# ONTVANGER.net
KiCad netlist of a schematic drawn in Altium Designer
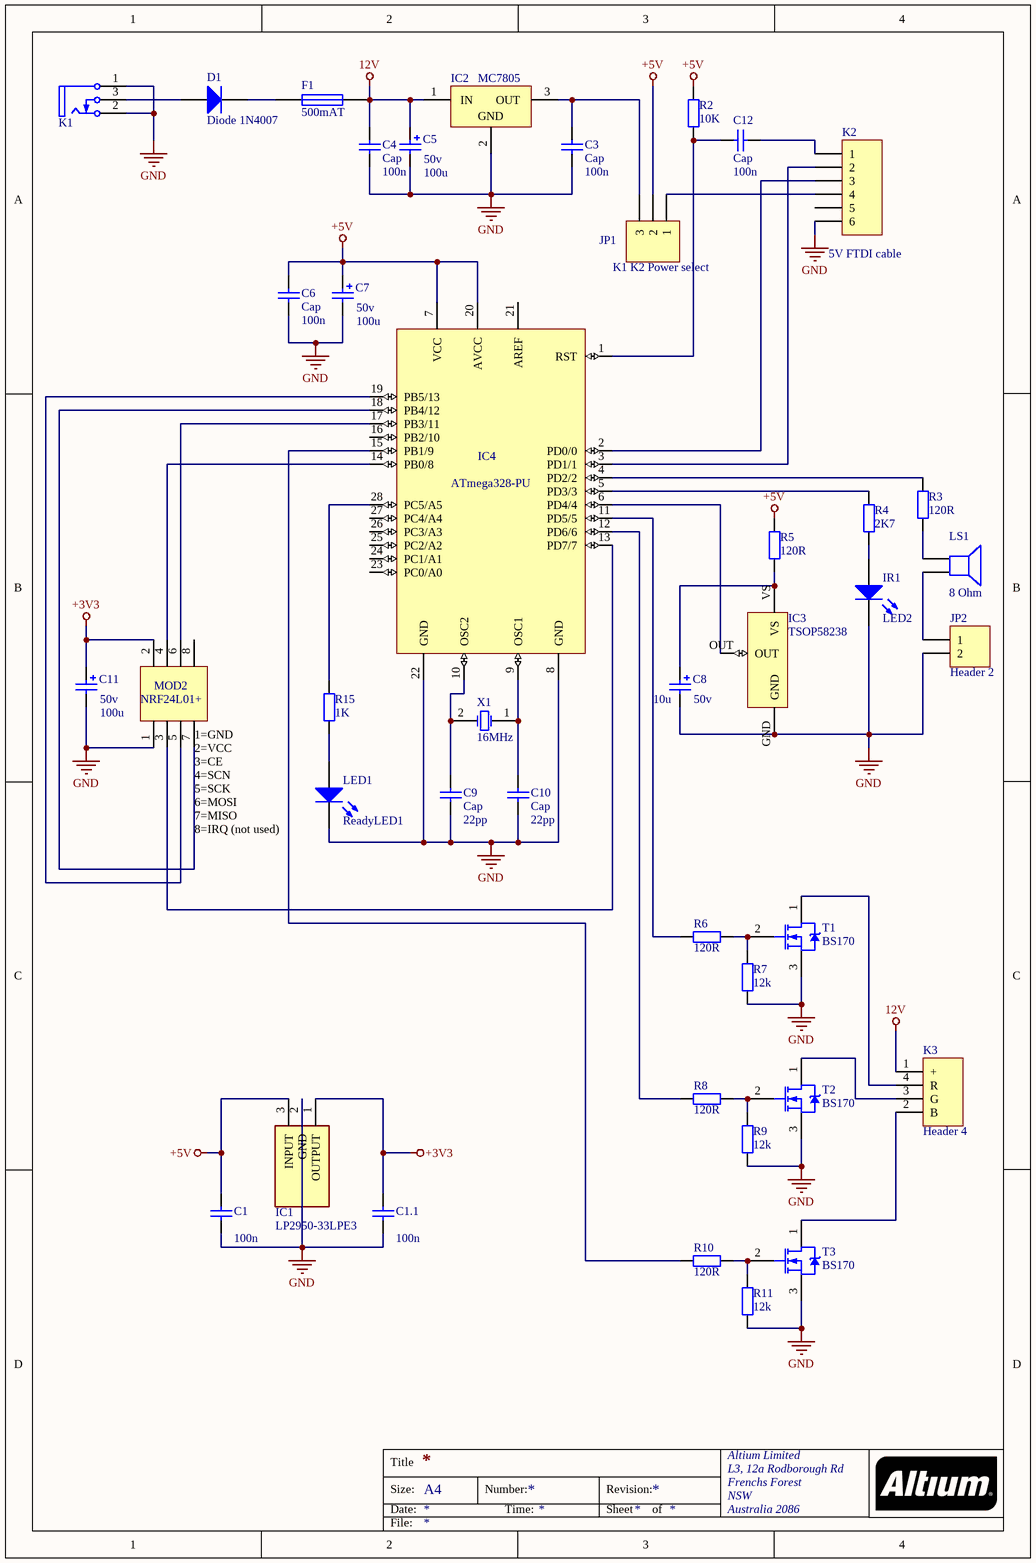
[diagram p0: ONTVANGER.SchDoc]

(export (version "E")
  (design (tool "Eeschema 10.0.6"))
  (components
    (comp (ref "C1")
      (value "100n")
      (footprint "RAD-0.3")
      (description "Capacitor")
      (fields (field (name "Comment") "Cap") (field (name "PUBLISHER") "Altium Limited"))
      (libsource (lib "Miscellaneous Devices") (part "Cap"))
    )
    (comp (ref "C1.1")
      (value "100n")
      (footprint "RAD-0.3")
      (description "Capacitor")
      (fields (field (name "Comment") "Cap") (field (name "PUBLISHER") "Altium Limited"))
      (libsource (lib "Miscellaneous Devices") (part "Cap"))
    )
    (comp (ref "C3")
      (value "Cap")
      (footprint "RAD-0.3")
      (description "Capacitor")
      (fields (field (name "ALTIUM_VALUE") "100n") (field (name "PUBLISHER") "Altium Limited"))
      (libsource (lib "Miscellaneous Devices") (part "Cap"))
    )
    (comp (ref "C4")
      (value "Cap")
      (footprint "RAD-0.3")
      (description "Capacitor")
      (fields (field (name "ALTIUM_VALUE") "100n") (field (name "PUBLISHER") "Altium Limited"))
      (libsource (lib "Miscellaneous Devices") (part "Cap"))
    )
    (comp (ref "C5")
      (value "50v")
      (footprint "POLAR0.8")
      (description "Polarized Capacitor (Axial)")
      (fields (field (name "ALTIUM_VALUE") "100u") (field (name "PUBLISHER") "Altium Limited"))
      (libsource (lib "Miscellaneous Devices") (part "Cap Pol2"))
    )
    (comp (ref "C6")
      (value "Cap")
      (footprint "RAD-0.3")
      (description "Capacitor")
      (fields (field (name "ALTIUM_VALUE") "100n") (field (name "PUBLISHER") "Altium Limited"))
      (libsource (lib "Miscellaneous Devices") (part "Cap"))
    )
    (comp (ref "C7")
      (value "50v")
      (footprint "POLAR0.8")
      (description "Polarized Capacitor (Axial)")
      (fields (field (name "ALTIUM_VALUE") "100u") (field (name "PUBLISHER") "Altium Limited"))
      (libsource (lib "Miscellaneous Devices") (part "Cap Pol2"))
    )
    (comp (ref "C8")
      (value "50v")
      (footprint "POLAR0.8")
      (description "Polarized Capacitor (Axial)")
      (fields (field (name "ALTIUM_VALUE") "10u") (field (name "PUBLISHER") "Altium Limited"))
      (libsource (lib "Miscellaneous Devices") (part "Cap Pol2"))
    )
    (comp (ref "C9")
      (value "Cap")
      (footprint "RAD-0.3")
      (description "Capacitor")
      (fields (field (name "ALTIUM_VALUE") "22pp") (field (name "PUBLISHER") "Altium Limited"))
      (libsource (lib "Miscellaneous Devices") (part "Cap"))
    )
    (comp (ref "C10")
      (value "Cap")
      (footprint "RAD-0.3")
      (description "Capacitor")
      (fields (field (name "ALTIUM_VALUE") "22pp") (field (name "PUBLISHER") "Altium Limited"))
      (libsource (lib "Miscellaneous Devices") (part "Cap"))
    )
    (comp (ref "C11")
      (value "50v")
      (footprint "POLAR0.8")
      (description "Polarized Capacitor (Axial)")
      (fields (field (name "ALTIUM_VALUE") "100u") (field (name "PUBLISHER") "Altium Limited"))
      (libsource (lib "Miscellaneous Devices") (part "Cap Pol2"))
    )
    (comp (ref "C12")
      (value "Cap")
      (footprint "RAD-0.3")
      (description "Capacitor")
      (fields (field (name "ALTIUM_VALUE") "100n") (field (name "PUBLISHER") "Altium Limited"))
      (libsource (lib "Miscellaneous Devices") (part "Cap"))
    )
    (comp (ref "D1")
      (value "Diode 1N4007")
      (footprint "DO-41")
      (description "1 Amp General Purpose Rectifier")
      (fields (field (name "PUBLISHER") "Altium Limited"))
      (libsource (lib "Miscellaneous Devices") (part "Diode 1N4007"))
    )
    (comp (ref "F1")
      (value "500mAT")
      (footprint "PIN-W2/E2.8")
      (description "Fuse")
      (fields (field (name "PUBLISHER") "Altium Limited"))
      (libsource (lib "Miscellaneous Devices") (part "Fuse 1"))
    )
    (comp (ref "IC1")
      (value "LP2950-33LPE3")
      (footprint "SamacSys:TO127P419X482X788-3P")
      (description "Integrated Circuit")
      (fields
        (field (name "MOUSER PART NUMBER") "595-LP2950-33LPE3")
        (field (name "RS PART NUMBER") "7620430P")
      )
      (libsource (lib "*") (part "LP2950-33LPE3"))
    )
    (comp (ref "IC2")
      (value "MC7805")
      (footprint "ONSC-TO-220-3-221AB-01")
      (description "Positive Voltage Regulator, 1 A, 5 V, 0 to 125 degC, 3-Pin TO-220, RoHS, Tube")
      (fields (field (name "MANUFACTURER") "ON Semiconductor"))
      (libsource (lib "Altium Content Vault") (part "ONSC-MC7805CTG-TO-220-3"))
    )
    (comp (ref "IC3")
      (value "TSOP58238")
      (footprint "*TSOP-382_TSOP38238(Primary)")
      (description "IR Receiver Modules for Remote Control System, 2.5 to 5.5 V, -25 to 85 degC, 3-Pin THD, RoHS, Bulk")
      (fields (field (name "TOLERANCE") "30ppm") (field (name "MANUFACTURER") "Vishay"))
      (libsource (lib "PCB_Project_1") (part "CMP-1666-00022-1"))
    )
    (comp (ref "IC4")
      (value "ATmega328-PU")
      (footprint "*DIL28")
      (fields
        (field (name "MANUFACTURER") "Microchip / Atmel")
        (field (name "MANUFACTURER PART NUMBER") "ATMEGA328-PU")
      )
      (libsource (lib "PCB_Project") (part "CMP-0095-00015-2"))
    )
    (comp (ref "IR1")
      (value "LED2")
      (footprint "LED-0")
      (description "Typical INFRARED GaAs LED")
      (fields (field (name "PUBLISHER") "Altium Limited"))
      (libsource (lib "Miscellaneous Devices") (part "LED0"))
    )
    (comp (ref "JP1")
      (value "K1 K2 Power select")
      (footprint "HDR1X3")
      (description "Header, 3-Pin")
      (fields (field (name "PUBLISHER") "Altium Limited"))
      (libsource (lib "Miscellaneous Connectors") (part "Header 3"))
    )
    (comp (ref "JP2")
      (value "Header 2")
      (footprint "HDR1X2")
      (description "Header, 2-Pin")
      (fields (field (name "PUBLISHER") "Altium Limited"))
      (libsource (lib "Miscellaneous Connectors") (part "Header 2"))
    )
    (comp (ref "K1")
      (value "PJRAN1X1U01X")
      (footprint "SWIT-PJRAN1X1U01X_V")
      (description "Female Phono Jack, 3 Position, Height 13 mm, Tail Length 4 mm, RoHS, Bulk")
      (fields (field (name "TOLERANCE") "10%"))
      (libsource (lib "Altium Content Vault") (part "JACK-2CD3-TN"))
    )
    (comp (ref "K2")
      (value "5V FTDI cable")
      (footprint "HDR1X6")
      (description "Header, 6-Pin")
      (fields (field (name "PUBLISHER") "Altium Limited"))
      (libsource (lib "Miscellaneous Connectors") (part "Header 6"))
    )
    (comp (ref "K3")
      (value "Header 4")
      (footprint "HDR1X4")
      (description "Header, 4-Pin")
      (fields (field (name "PUBLISHER") "Altium Limited"))
      (libsource (lib "Miscellaneous Connectors") (part "Header 4"))
    )
    (comp (ref "LS1")
      (value "8 Ohm")
      (footprint "PIN2")
      (description "Loudspeaker")
      (fields (field (name "PUBLISHER") "Altium Limited"))
      (libsource (lib "Miscellaneous Devices") (part "Speaker"))
    )
    (comp (ref "MOD2")
      (value "NRF24L01+")
      (footprint "HDR2X4")
      (description "Header, 4-Pin, Dual row")
      (fields (field (name "PUBLISHER") "Altium Limited"))
      (libsource (lib "Miscellaneous Connectors") (part "Header 4X2"))
    )
    (comp (ref "R2")
      (value "10K")
      (footprint "*RESC3115X70N")
      (description "Resistor")
      (fields (field (name "Comment") "Res2") (field (name "PUBLISHER") "Altium Limited"))
      (libsource (lib "PCB_Project") (part "Res2"))
    )
    (comp (ref "R3")
      (value "120R")
      (footprint "*RESC3146X60N")
      (description "Resistor")
      (fields (field (name "Comment") "Res2") (field (name "PUBLISHER") "Altium Limited"))
      (libsource (lib "PCB_Project") (part "Res2"))
    )
    (comp (ref "R4")
      (value "2K7")
      (footprint "*RESC3215X64N")
      (description "Resistor")
      (fields (field (name "Comment") "Res2") (field (name "PUBLISHER") "Altium Limited"))
      (libsource (lib "PCB_Project") (part "Res2"))
    )
    (comp (ref "R5")
      (value "120R")
      (footprint "*RESC3146X60N")
      (description "Resistor")
      (fields (field (name "Comment") "Res2") (field (name "PUBLISHER") "Altium Limited"))
      (libsource (lib "PCB_Project") (part "Res2"))
    )
    (comp (ref "R6")
      (value "120R")
      (footprint "*RESC3146X60N")
      (description "Resistor")
      (fields (field (name "Comment") "Res2") (field (name "PUBLISHER") "Altium Limited"))
      (libsource (lib "") (part "Res2_1"))
    )
    (comp (ref "R7")
      (value "12k")
      (footprint "*RESC3215X64N")
      (description "Resistor")
      (fields (field (name "Comment") "Res2") (field (name "PUBLISHER") "Altium Limited"))
      (libsource (lib "PCB_Project") (part "Res2"))
    )
    (comp (ref "R8")
      (value "120R")
      (footprint "*RESC3146X60N")
      (description "Resistor")
      (fields (field (name "Comment") "Res2") (field (name "PUBLISHER") "Altium Limited"))
      (libsource (lib "") (part "Res2_1"))
    )
    (comp (ref "R9")
      (value "12k")
      (footprint "*RESC3215X64N")
      (description "Resistor")
      (fields (field (name "Comment") "Res2") (field (name "PUBLISHER") "Altium Limited"))
      (libsource (lib "PCB_Project") (part "Res2"))
    )
    (comp (ref "R10")
      (value "120R")
      (footprint "*RESC3146X60N")
      (description "Resistor")
      (fields (field (name "Comment") "Res2") (field (name "PUBLISHER") "Altium Limited"))
      (libsource (lib "") (part "Res2_1"))
    )
    (comp (ref "R11")
      (value "12k")
      (footprint "*RESC3215X64N")
      (description "Resistor")
      (fields (field (name "Comment") "Res2") (field (name "PUBLISHER") "Altium Limited"))
      (libsource (lib "PCB_Project") (part "Res2"))
    )
    (comp (ref "R15")
      (value "1K")
      (footprint "*RESC1412X64N")
      (description "Resistor")
      (fields (field (name "Comment") "Res2") (field (name "PUBLISHER") "Altium Limited"))
      (libsource (lib "PCB_Project") (part "Res2"))
    )
    (comp (ref "ReadyLED1")
      (value "LED1")
      (footprint "LED-0")
      (description "Typical INFRARED GaAs LED")
      (fields (field (name "PUBLISHER") "Altium Limited"))
      (libsource (lib "Miscellaneous Devices") (part "LED0"))
    )
    (comp (ref "T1")
      (value "BS170")
      (footprint "ONSC-TO-92-3-29-11")
      (description "Small Signal MOSFET, 500 mA, 60 V, N-Channel, 3-Pin TO-92, Bulk Box")
      (fields (field (name "MANUFACTURER") "On Semiconductor"))
      (libsource (lib "Altium Content Vault") (part "ONSC-NMOS-D1G2S3-3"))
    )
    (comp (ref "T2")
      (value "BS170")
      (footprint "ONSC-TO-92-3-29-11")
      (description "Small Signal MOSFET, 500 mA, 60 V, N-Channel, 3-Pin TO-92, Bulk Box")
      (fields (field (name "MANUFACTURER") "On Semiconductor"))
      (libsource (lib "Altium Content Vault") (part "ONSC-NMOS-D1G2S3-3"))
    )
    (comp (ref "T3")
      (value "BS170")
      (footprint "ONSC-TO-92-3-29-11")
      (description "Small Signal MOSFET, 500 mA, 60 V, N-Channel, 3-Pin TO-92, Bulk Box")
      (fields (field (name "MANUFACTURER") "On Semiconductor"))
      (libsource (lib "Altium Content Vault") (part "ONSC-NMOS-D1G2S3-3"))
    )
    (comp (ref "X1")
      (value "16MHz")
      (footprint "R38")
      (description "RALTRON - AS-16.000-18 - CRYSTAL, 16MHZ, 18PF, HC-49S")
      (fields
        (field (name "MANUFACTURER") "Raltron Electronics")
        (field (name "MANUFACTURER PART NUMBER") "AS-16.000-18")
        (field (name "PUBLISHER") "Altium Limited")
      )
      (libsource (lib "Miscellaneous Devices") (part "XTAL"))
    )
  )
  (nets
    (net (code "1") (name "+3V3") (class "Default")
      (node (ref "C1.1") (pin "2") (pinfunction "2_2") (pintype "passive"))
      (node (ref "C11") (pin "1") (pinfunction "1_1") (pintype "passive"))
      (node (ref "IC1") (pin "1") (pinfunction "OUTPUT_1") (pintype "passive"))
      (node (ref "MOD2") (pin "2") (pintype "passive"))
    )
    (net (code "2") (name "+5V") (class "Default")
      (node (ref "C1") (pin "2") (pinfunction "2_2") (pintype "passive"))
      (node (ref "C6") (pin "2") (pinfunction "2_2") (pintype "passive"))
      (node (ref "C7") (pin "1") (pinfunction "1_1") (pintype "passive"))
      (node (ref "IC1") (pin "3") (pinfunction "INPUT_3") (pintype "passive"))
      (node (ref "IC4") (pin "20") (pinfunction "AVCC_20") (pintype "power_in"))
      (node (ref "IC4") (pin "7") (pinfunction "VCC_7") (pintype "power_in"))
      (node (ref "JP1") (pin "2") (pinfunction "2_2") (pintype "passive"))
      (node (ref "R2") (pin "2") (pinfunction "2_2") (pintype "passive"))
      (node (ref "R5") (pin "2") (pinfunction "2_2") (pintype "passive"))
    )
    (net (code "3") (name "12V") (class "Default")
      (node (ref "C4") (pin "2") (pinfunction "2_2") (pintype "passive"))
      (node (ref "C5") (pin "1") (pinfunction "1_1") (pintype "passive"))
      (node (ref "F1") (pin "2") (pinfunction "2_2") (pintype "passive"))
      (node (ref "IC2") (pin "1") (pinfunction "IN_1") (pintype "power_in"))
      (node (ref "K3") (pin "1") (pinfunction "+_1") (pintype "passive"))
    )
    (net (code "4") (name "GND") (class "Default")
      (node (ref "C1") (pin "1") (pinfunction "1_1") (pintype "passive"))
      (node (ref "C1.1") (pin "1") (pinfunction "1_1") (pintype "passive"))
      (node (ref "C10") (pin "1") (pinfunction "1_1") (pintype "passive"))
      (node (ref "C11") (pin "2") (pinfunction "2_2") (pintype "passive"))
      (node (ref "C3") (pin "1") (pinfunction "1_1") (pintype "passive"))
      (node (ref "C4") (pin "1") (pinfunction "1_1") (pintype "passive"))
      (node (ref "C5") (pin "2") (pinfunction "2_2") (pintype "passive"))
      (node (ref "C6") (pin "1") (pinfunction "1_1") (pintype "passive"))
      (node (ref "C7") (pin "2") (pinfunction "2_2") (pintype "passive"))
      (node (ref "C8") (pin "2") (pinfunction "2_2") (pintype "passive"))
      (node (ref "C9") (pin "1") (pinfunction "1_1") (pintype "passive"))
      (node (ref "IC1") (pin "2") (pinfunction "GND_2") (pintype "passive"))
      (node (ref "IC2") (pin "2") (pinfunction "GND_2") (pintype "power_in"))
      (node (ref "IC3") (pin "GND") (pinfunction "GND_GND") (pintype "power_in"))
      (node (ref "IC4") (pin "22") (pinfunction "GND_22") (pintype "power_in"))
      (node (ref "IC4") (pin "8") (pinfunction "GND_8") (pintype "power_in"))
      (node (ref "IR1") (pin "2") (pinfunction "K_2") (pintype "passive"))
      (node (ref "JP2") (pin "2") (pinfunction "2_2") (pintype "passive"))
      (node (ref "K1") (pin "1") (pinfunction "SLEEVE_1") (pintype "passive"))
      (node (ref "K1") (pin "2") (pinfunction "TIP_2") (pintype "passive"))
      (node (ref "K2") (pin "6") (pinfunction "6_6") (pintype "passive"))
      (node (ref "MOD2") (pin "1") (pintype "passive"))
      (node (ref "R11") (pin "1") (pinfunction "1_1") (pintype "passive"))
      (node (ref "R7") (pin "1") (pinfunction "1_1") (pintype "passive"))
      (node (ref "R9") (pin "1") (pinfunction "1_1") (pintype "passive"))
      (node (ref "ReadyLED1") (pin "2") (pinfunction "K_2") (pintype "passive"))
      (node (ref "T1") (pin "3") (pinfunction "S_3") (pintype "passive"))
      (node (ref "T2") (pin "3") (pinfunction "S_3") (pintype "passive"))
      (node (ref "T3") (pin "3") (pinfunction "S_3") (pintype "passive"))
    )
    (net (code "5") (name "Net-(C8-Pad1)") (class "Default")
      (node (ref "C8") (pin "1") (pinfunction "1_1") (pintype "passive"))
      (node (ref "IC3") (pin "VS") (pinfunction "VS_VS") (pintype "power_in"))
      (node (ref "R5") (pin "1") (pinfunction "1_1") (pintype "passive"))
    )
    (net (code "6") (name "Net-(C12-Pad1)") (class "Default")
      (node (ref "C12") (pin "1") (pinfunction "1_1") (pintype "passive"))
      (node (ref "K2") (pin "1") (pinfunction "1_1") (pintype "passive"))
    )
    (net (code "7") (name "Net-(D1-A)") (class "Default")
      (node (ref "D1") (pin "1") (pinfunction "A_1") (pintype "passive"))
      (node (ref "K1") (pin "3") (pinfunction "SHUNT_3") (pintype "passive"))
    )
    (net (code "8") (name "Net-(D1-K)") (class "Default")
      (node (ref "D1") (pin "2") (pinfunction "K_2") (pintype "passive"))
      (node (ref "F1") (pin "1") (pinfunction "1_1") (pintype "passive"))
    )
    (net (code "9") (name "Net-(IC2-OUT)") (class "Default")
      (node (ref "C3") (pin "2") (pinfunction "2_2") (pintype "passive"))
      (node (ref "IC2") (pin "3") (pinfunction "OUT_3") (pintype "power_in"))
      (node (ref "JP1") (pin "3") (pinfunction "3_3") (pintype "passive"))
    )
    (net (code "10") (name "Net-(IC4-OSC1)") (class "Default")
      (node (ref "C10") (pin "2") (pinfunction "2_2") (pintype "passive"))
      (node (ref "IC4") (pin "9") (pinfunction "OSC1_9") (pintype "bidirectional"))
      (node (ref "X1") (pin "1") (pinfunction "OSC1_1") (pintype "passive"))
    )
    (net (code "11") (name "Net-(IC4-OSC2)") (class "Default")
      (node (ref "C9") (pin "2") (pinfunction "2_2") (pintype "passive"))
      (node (ref "IC4") (pin "10") (pinfunction "OSC2_10") (pintype "bidirectional"))
      (node (ref "X1") (pin "2") (pinfunction "OSC2_2") (pintype "passive"))
    )
    (net (code "12") (name "Net-(IC4-PB0{slash}8)") (class "Default")
      (node (ref "IC4") (pin "14") (pinfunction "PB0/8_14") (pintype "bidirectional"))
      (node (ref "MOD2") (pin "4") (pintype "passive"))
    )
    (net (code "13") (name "Net-(IC4-PB1{slash}9)") (class "Default")
      (node (ref "IC4") (pin "15") (pinfunction "PB1/9_15") (pintype "bidirectional"))
      (node (ref "R10") (pin "2") (pinfunction "2_2") (pintype "passive"))
    )
    (net (code "14") (name "Net-(IC4-PB3{slash}11)") (class "Default")
      (node (ref "IC4") (pin "17") (pinfunction "PB3/11_17") (pintype "bidirectional"))
      (node (ref "MOD2") (pin "6") (pintype "passive"))
    )
    (net (code "15") (name "Net-(IC4-PB4{slash}12)") (class "Default")
      (node (ref "IC4") (pin "18") (pinfunction "PB4/12_18") (pintype "bidirectional"))
      (node (ref "MOD2") (pin "7") (pintype "passive"))
    )
    (net (code "16") (name "Net-(IC4-PB5{slash}13)") (class "Default")
      (node (ref "IC4") (pin "19") (pinfunction "PB5/13_19") (pintype "bidirectional"))
      (node (ref "MOD2") (pin "5") (pintype "passive"))
    )
    (net (code "17") (name "Net-(IC4-PC5{slash}A5)") (class "Default")
      (node (ref "IC4") (pin "28") (pinfunction "PC5/A5_28") (pintype "bidirectional"))
      (node (ref "R15") (pin "2") (pinfunction "2_2") (pintype "passive"))
    )
    (net (code "18") (name "Net-(IC4-PD0{slash}0)") (class "Default")
      (node (ref "IC4") (pin "2") (pinfunction "PD0/0_2") (pintype "bidirectional"))
      (node (ref "K2") (pin "3") (pinfunction "3_3") (pintype "passive"))
    )
    (net (code "19") (name "Net-(IC4-PD1{slash}1)") (class "Default")
      (node (ref "IC4") (pin "3") (pinfunction "PD1/1_3") (pintype "bidirectional"))
      (node (ref "K2") (pin "2") (pinfunction "2_2") (pintype "passive"))
    )
    (net (code "20") (name "Net-(IC4-PD2{slash}2)") (class "Default")
      (node (ref "IC4") (pin "4") (pinfunction "PD2/2_4") (pintype "bidirectional"))
      (node (ref "R3") (pin "2") (pinfunction "2_2") (pintype "passive"))
    )
    (net (code "21") (name "Net-(IC4-PD3{slash}3)") (class "Default")
      (node (ref "IC4") (pin "5") (pinfunction "PD3/3_5") (pintype "bidirectional"))
      (node (ref "R4") (pin "2") (pinfunction "2_2") (pintype "passive"))
    )
    (net (code "22") (name "Net-(IC4-PD4{slash}4)") (class "Default")
      (node (ref "IC3") (pin "OUT") (pinfunction "OUT_OUT") (pintype "bidirectional"))
      (node (ref "IC4") (pin "6") (pinfunction "PD4/4_6") (pintype "bidirectional"))
    )
    (net (code "23") (name "Net-(IC4-PD5{slash}5)") (class "Default")
      (node (ref "IC4") (pin "11") (pinfunction "PD5/5_11") (pintype "bidirectional"))
      (node (ref "R6") (pin "2") (pinfunction "2_2") (pintype "passive"))
    )
    (net (code "24") (name "Net-(IC4-PD6{slash}6)") (class "Default")
      (node (ref "IC4") (pin "12") (pinfunction "PD6/6_12") (pintype "bidirectional"))
      (node (ref "R8") (pin "2") (pinfunction "2_2") (pintype "passive"))
    )
    (net (code "25") (name "Net-(IC4-PD7{slash}7)") (class "Default")
      (node (ref "IC4") (pin "13") (pinfunction "PD7/7_13") (pintype "bidirectional"))
      (node (ref "MOD2") (pin "3") (pintype "passive"))
    )
    (net (code "26") (name "Net-(IC4-RST)") (class "Default")
      (node (ref "C12") (pin "2") (pinfunction "2_2") (pintype "passive"))
      (node (ref "IC4") (pin "1") (pinfunction "RST_1") (pintype "bidirectional"))
      (node (ref "R2") (pin "1") (pinfunction "1_1") (pintype "passive"))
    )
    (net (code "27") (name "Net-(IR1-A)") (class "Default")
      (node (ref "IR1") (pin "1") (pinfunction "A_1") (pintype "passive"))
      (node (ref "R4") (pin "1") (pinfunction "1_1") (pintype "passive"))
    )
    (net (code "28") (name "Net-(JP1-Pad1)") (class "Default")
      (node (ref "JP1") (pin "1") (pinfunction "1_1") (pintype "passive"))
      (node (ref "K2") (pin "4") (pinfunction "4_4") (pintype "passive"))
    )
    (net (code "29") (name "Net-(JP2-Pad1)") (class "Default")
      (node (ref "JP2") (pin "1") (pinfunction "1_1") (pintype "passive"))
      (node (ref "LS1") (pin "2") (pinfunction "2_2") (pintype "passive"))
    )
    (net (code "30") (name "Net-(K3-B)") (class "Default")
      (node (ref "K3") (pin "2") (pinfunction "B_2") (pintype "passive"))
      (node (ref "T3") (pin "1") (pinfunction "D_1") (pintype "passive"))
    )
    (net (code "31") (name "Net-(K3-G)") (class "Default")
      (node (ref "K3") (pin "3") (pinfunction "G_3") (pintype "passive"))
      (node (ref "T2") (pin "1") (pinfunction "D_1") (pintype "passive"))
    )
    (net (code "32") (name "Net-(K3-R)") (class "Default")
      (node (ref "K3") (pin "4") (pinfunction "R_4") (pintype "passive"))
      (node (ref "T1") (pin "1") (pinfunction "D_1") (pintype "passive"))
    )
    (net (code "33") (name "Net-(LS1-Pad1)") (class "Default")
      (node (ref "LS1") (pin "1") (pinfunction "1_1") (pintype "passive"))
      (node (ref "R3") (pin "1") (pinfunction "1_1") (pintype "passive"))
    )
    (net (code "34") (name "Net-(ReadyLED1-A)") (class "Default")
      (node (ref "R15") (pin "1") (pinfunction "1_1") (pintype "passive"))
      (node (ref "ReadyLED1") (pin "1") (pinfunction "A_1") (pintype "passive"))
    )
    (net (code "35") (name "Net-(T1-G)") (class "Default")
      (node (ref "R6") (pin "1") (pinfunction "1_1") (pintype "passive"))
      (node (ref "R7") (pin "2") (pinfunction "2_2") (pintype "passive"))
      (node (ref "T1") (pin "2") (pinfunction "G_2") (pintype "passive"))
    )
    (net (code "36") (name "Net-(T2-G)") (class "Default")
      (node (ref "R8") (pin "1") (pinfunction "1_1") (pintype "passive"))
      (node (ref "R9") (pin "2") (pinfunction "2_2") (pintype "passive"))
      (node (ref "T2") (pin "2") (pinfunction "G_2") (pintype "passive"))
    )
    (net (code "37") (name "Net-(T3-G)") (class "Default")
      (node (ref "R10") (pin "1") (pinfunction "1_1") (pintype "passive"))
      (node (ref "R11") (pin "2") (pinfunction "2_2") (pintype "passive"))
      (node (ref "T3") (pin "2") (pinfunction "G_2") (pintype "passive"))
    )
    (net (code "38") (name "unconnected-(IC4-AREF-Pad21)") (class "Default")
      (node (ref "IC4") (pin "21") (pinfunction "AREF_21") (pintype "power_in"))
    )
    (net (code "39") (name "unconnected-(IC4-PB2{slash}10-Pad16)") (class "Default")
      (node (ref "IC4") (pin "16") (pinfunction "PB2/10_16") (pintype "bidirectional"))
    )
    (net (code "40") (name "unconnected-(IC4-PC0{slash}A0-Pad23)") (class "Default")
      (node (ref "IC4") (pin "23") (pinfunction "PC0/A0_23") (pintype "bidirectional"))
    )
    (net (code "41") (name "unconnected-(IC4-PC1{slash}A1-Pad24)") (class "Default")
      (node (ref "IC4") (pin "24") (pinfunction "PC1/A1_24") (pintype "bidirectional"))
    )
    (net (code "42") (name "unconnected-(IC4-PC2{slash}A2-Pad25)") (class "Default")
      (node (ref "IC4") (pin "25") (pinfunction "PC2/A2_25") (pintype "bidirectional"))
    )
    (net (code "43") (name "unconnected-(IC4-PC3{slash}A3-Pad26)") (class "Default")
      (node (ref "IC4") (pin "26") (pinfunction "PC3/A3_26") (pintype "bidirectional"))
    )
    (net (code "44") (name "unconnected-(IC4-PC4{slash}A4-Pad27)") (class "Default")
      (node (ref "IC4") (pin "27") (pinfunction "PC4/A4_27") (pintype "bidirectional"))
    )
    (net (code "45") (name "unconnected-(K2-Pad5)") (class "Default")
      (node (ref "K2") (pin "5") (pinfunction "5_5") (pintype "passive"))
    )
    (net (code "46") (name "unconnected-(MOD2-Pad8)") (class "Default")
      (node (ref "MOD2") (pin "8") (pintype "passive"))
    )
  )
)
